# cardprog4040.net
KiCad netlist of a schematic drawn in EAGLE
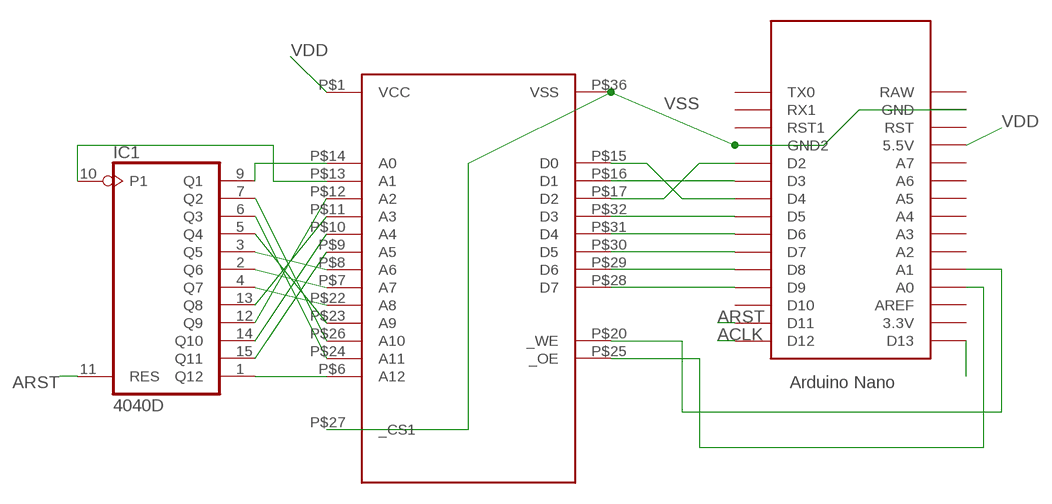
[diagram p0: schematic, sheet 1]

(export (version "E")
  (design (tool "Eeschema 10.0.6"))
  (components
    (comp (ref "IC1")
      (value "4040D")
      (footprint "eagle-import:SO16")
      (libsource (lib "eagle-import") (part "4040D"))
    )
    (comp (ref "U$1")
      (value "NANO")
      (footprint "eagle-import:NANO")
      (libsource (lib "eagle-import") (part "NANO"))
    )
    (comp (ref "U$2")
      (value "28C64SLOT")
      (footprint "eagle-import:SLOT36")
      (libsource (lib "eagle-import") (part "28C64SLOT"))
    )
  )
  (nets
    (net (code "1") (name "/ACLK") (class "Default")
      (node (ref "IC1") (pin "10") (pinfunction "P1_10") (pintype "input"))
      (node (ref "U$1") (pin "D12") (pinfunction "D12_D12") (pintype "bidirectional"))
      (node (ref "U$2") (pin "P$13") (pinfunction "A1_P$13") (pintype "input"))
    )
    (net (code "2") (name "/ARST") (class "Default")
      (node (ref "IC1") (pin "11") (pinfunction "RES_11") (pintype "input"))
      (node (ref "U$1") (pin "D11") (pinfunction "D11_D11") (pintype "bidirectional"))
    )
    (net (code "3") (name "/VDD") (class "Default")
      (node (ref "U$1") (pin "5V") (pinfunction "5.5V_5V") (pintype "bidirectional"))
      (node (ref "U$2") (pin "P$1") (pinfunction "VCC_P$1") (pintype "power_in"))
    )
    (net (code "4") (name "/VSS") (class "Default")
      (node (ref "U$1") (pin "GND") (pinfunction "GND_GND") (pintype "bidirectional"))
      (node (ref "U$1") (pin "GND1") (pinfunction "GND2_GND1") (pintype "bidirectional"))
      (node (ref "U$2") (pin "P$27") (pinfunction "_CS1_P$27") (pintype "input"))
      (node (ref "U$2") (pin "P$36") (pinfunction "VSS_P$36") (pintype "power_in"))
    )
    (net (code "5") (name "Net-(IC1A-Q1)") (class "Default")
      (node (ref "IC1") (pin "9") (pinfunction "Q1_9") (pintype "output"))
      (node (ref "U$2") (pin "P$14") (pinfunction "A0_P$14") (pintype "input"))
    )
    (net (code "6") (name "Net-(IC1A-Q2)") (class "Default")
      (node (ref "IC1") (pin "7") (pinfunction "Q2_7") (pintype "output"))
      (node (ref "U$2") (pin "P$26") (pinfunction "A10_P$26") (pintype "input"))
    )
    (net (code "7") (name "Net-(IC1A-Q3)") (class "Default")
      (node (ref "IC1") (pin "6") (pinfunction "Q3_6") (pintype "output"))
      (node (ref "U$2") (pin "P$24") (pinfunction "A11_P$24") (pintype "input"))
    )
    (net (code "8") (name "Net-(IC1A-Q4)") (class "Default")
      (node (ref "IC1") (pin "5") (pinfunction "Q4_5") (pintype "output"))
      (node (ref "U$2") (pin "P$23") (pinfunction "A9_P$23") (pintype "input"))
    )
    (net (code "9") (name "Net-(IC1A-Q5)") (class "Default")
      (node (ref "IC1") (pin "3") (pinfunction "Q5_3") (pintype "output"))
      (node (ref "U$2") (pin "P$8") (pinfunction "A6_P$8") (pintype "input"))
    )
    (net (code "10") (name "Net-(IC1A-Q6)") (class "Default")
      (node (ref "IC1") (pin "2") (pinfunction "Q6_2") (pintype "output"))
      (node (ref "U$2") (pin "P$7") (pinfunction "A7_P$7") (pintype "input"))
    )
    (net (code "11") (name "Net-(IC1A-Q7)") (class "Default")
      (node (ref "IC1") (pin "4") (pinfunction "Q7_4") (pintype "output"))
      (node (ref "U$2") (pin "P$22") (pinfunction "A8_P$22") (pintype "input"))
    )
    (net (code "12") (name "Net-(IC1A-Q8)") (class "Default")
      (node (ref "IC1") (pin "13") (pinfunction "Q8_13") (pintype "output"))
      (node (ref "U$2") (pin "P$11") (pinfunction "A3_P$11") (pintype "input"))
    )
    (net (code "13") (name "Net-(IC1A-Q9)") (class "Default")
      (node (ref "IC1") (pin "12") (pinfunction "Q9_12") (pintype "output"))
      (node (ref "U$2") (pin "P$12") (pinfunction "A2_P$12") (pintype "input"))
    )
    (net (code "14") (name "Net-(IC1A-Q10)") (class "Default")
      (node (ref "IC1") (pin "14") (pinfunction "Q10_14") (pintype "output"))
      (node (ref "U$2") (pin "P$10") (pinfunction "A4_P$10") (pintype "input"))
    )
    (net (code "15") (name "Net-(IC1A-Q11)") (class "Default")
      (node (ref "IC1") (pin "15") (pinfunction "Q11_15") (pintype "output"))
      (node (ref "U$2") (pin "P$9") (pinfunction "A5_P$9") (pintype "input"))
    )
    (net (code "16") (name "Net-(IC1A-Q12)") (class "Default")
      (node (ref "IC1") (pin "1") (pinfunction "Q12_1") (pintype "output"))
      (node (ref "U$2") (pin "P$6") (pinfunction "A12_P$6") (pintype "input"))
    )
    (net (code "17") (name "Net-(U$2-D0)") (class "Default")
      (node (ref "U$1") (pin "D4") (pinfunction "D4_D4") (pintype "bidirectional"))
      (node (ref "U$2") (pin "P$15") (pinfunction "D0_P$15") (pintype "bidirectional"))
    )
    (net (code "18") (name "Net-(U$2-D1)") (class "Default")
      (node (ref "U$1") (pin "D3") (pinfunction "D3_D3") (pintype "bidirectional"))
      (node (ref "U$2") (pin "P$16") (pinfunction "D1_P$16") (pintype "bidirectional"))
    )
    (net (code "19") (name "Net-(U$2-D2)") (class "Default")
      (node (ref "U$1") (pin "D2") (pinfunction "D2_D2") (pintype "bidirectional"))
      (node (ref "U$2") (pin "P$17") (pinfunction "D2_P$17") (pintype "bidirectional"))
    )
    (net (code "20") (name "Net-(U$2-D3)") (class "Default")
      (node (ref "U$1") (pin "D5") (pinfunction "D5_D5") (pintype "bidirectional"))
      (node (ref "U$2") (pin "P$32") (pinfunction "D3_P$32") (pintype "bidirectional"))
    )
    (net (code "21") (name "Net-(U$2-D4)") (class "Default")
      (node (ref "U$1") (pin "D6") (pinfunction "D6_D6") (pintype "bidirectional"))
      (node (ref "U$2") (pin "P$31") (pinfunction "D4_P$31") (pintype "bidirectional"))
    )
    (net (code "22") (name "Net-(U$2-D5)") (class "Default")
      (node (ref "U$1") (pin "D7") (pinfunction "D7_D7") (pintype "bidirectional"))
      (node (ref "U$2") (pin "P$30") (pinfunction "D5_P$30") (pintype "bidirectional"))
    )
    (net (code "23") (name "Net-(U$2-D6)") (class "Default")
      (node (ref "U$1") (pin "D8") (pinfunction "D8_D8") (pintype "bidirectional"))
      (node (ref "U$2") (pin "P$29") (pinfunction "D6_P$29") (pintype "bidirectional"))
    )
    (net (code "24") (name "Net-(U$2-D7)") (class "Default")
      (node (ref "U$1") (pin "D9") (pinfunction "D9_D9") (pintype "bidirectional"))
      (node (ref "U$2") (pin "P$28") (pinfunction "D7_P$28") (pintype "bidirectional"))
    )
    (net (code "25") (name "Net-(U$2-_OE)") (class "Default")
      (node (ref "U$1") (pin "A0") (pinfunction "A0_A0") (pintype "bidirectional"))
      (node (ref "U$2") (pin "P$25") (pinfunction "_OE_P$25") (pintype "input"))
    )
    (net (code "26") (name "Net-(U$2-_WE)") (class "Default")
      (node (ref "U$1") (pin "A1") (pinfunction "A1_A1") (pintype "bidirectional"))
      (node (ref "U$2") (pin "P$20") (pinfunction "_WE_P$20") (pintype "input"))
    )
    (net (code "27") (name "unconnected-(U$1-Pad3.3V)") (class "Default")
      (node (ref "U$1") (pin "3.3V") (pinfunction "3.3V_3.3V") (pintype "bidirectional"))
    )
    (net (code "28") (name "unconnected-(U$1-PadA2)") (class "Default")
      (node (ref "U$1") (pin "A2") (pinfunction "A2_A2") (pintype "bidirectional"))
    )
    (net (code "29") (name "unconnected-(U$1-PadA3)") (class "Default")
      (node (ref "U$1") (pin "A3") (pinfunction "A3_A3") (pintype "bidirectional"))
    )
    (net (code "30") (name "unconnected-(U$1-PadA4)") (class "Default")
      (node (ref "U$1") (pin "A4") (pinfunction "A4_A4") (pintype "bidirectional"))
    )
    (net (code "31") (name "unconnected-(U$1-PadA5)") (class "Default")
      (node (ref "U$1") (pin "A5") (pinfunction "A5_A5") (pintype "bidirectional"))
    )
    (net (code "32") (name "unconnected-(U$1-PadA6)") (class "Default")
      (node (ref "U$1") (pin "A6") (pinfunction "A6_A6") (pintype "bidirectional"))
    )
    (net (code "33") (name "unconnected-(U$1-PadA7)") (class "Default")
      (node (ref "U$1") (pin "A7") (pinfunction "A7_A7") (pintype "bidirectional"))
    )
    (net (code "34") (name "unconnected-(U$1-PadAREF)") (class "Default")
      (node (ref "U$1") (pin "AREF") (pinfunction "AREF_AREF") (pintype "bidirectional"))
    )
    (net (code "35") (name "unconnected-(U$1-PadD10)") (class "Default")
      (node (ref "U$1") (pin "D10") (pinfunction "D10_D10") (pintype "bidirectional"))
    )
    (net (code "36") (name "unconnected-(U$1-PadD13)") (class "Default")
      (node (ref "U$1") (pin "D13") (pinfunction "D13_D13") (pintype "bidirectional"))
    )
    (net (code "37") (name "unconnected-(U$1-PadICSP1)") (class "Default")
      (node (ref "U$1") (pin "ICSP1") (pinfunction "ICSP1_ICSP1") (pintype "bidirectional"))
    )
    (net (code "38") (name "unconnected-(U$1-PadICSP2)") (class "Default")
      (node (ref "U$1") (pin "ICSP2") (pinfunction "ICSP2_ICSP2") (pintype "bidirectional"))
    )
    (net (code "39") (name "unconnected-(U$1-PadICSP3)") (class "Default")
      (node (ref "U$1") (pin "ICSP3") (pinfunction "ICSP3_ICSP3") (pintype "bidirectional"))
    )
    (net (code "40") (name "unconnected-(U$1-PadICSP4)") (class "Default")
      (node (ref "U$1") (pin "ICSP4") (pinfunction "ICSP4_ICSP4") (pintype "bidirectional"))
    )
    (net (code "41") (name "unconnected-(U$1-PadICSP5)") (class "Default")
      (node (ref "U$1") (pin "ICSP5") (pinfunction "ICSP5_ICSP5") (pintype "bidirectional"))
    )
    (net (code "42") (name "unconnected-(U$1-PadICSP6)") (class "Default")
      (node (ref "U$1") (pin "ICSP6") (pinfunction "ICSP6_ICSP6") (pintype "bidirectional"))
    )
    (net (code "43") (name "unconnected-(U$1-PadRAW)") (class "Default")
      (node (ref "U$1") (pin "RAW") (pinfunction "RAW_RAW") (pintype "bidirectional"))
    )
    (net (code "44") (name "unconnected-(U$1-PadRST)") (class "Default")
      (node (ref "U$1") (pin "RST") (pinfunction "RST_RST") (pintype "bidirectional"))
    )
    (net (code "45") (name "unconnected-(U$1-PadRST1)") (class "Default")
      (node (ref "U$1") (pin "RST1") (pinfunction "RST1_RST1") (pintype "bidirectional"))
    )
    (net (code "46") (name "unconnected-(U$1-PadRX1)") (class "Default")
      (node (ref "U$1") (pin "RX1") (pinfunction "RX1_RX1") (pintype "bidirectional"))
    )
    (net (code "47") (name "unconnected-(U$1-PadTX0)") (class "Default")
      (node (ref "U$1") (pin "TX0") (pinfunction "TX0_TX0") (pintype "bidirectional"))
    )
  )
)
